# SCH_NFC-Business-card_2025-08-31.net
KiCad netlist of a schematic drawn in EasyEDA
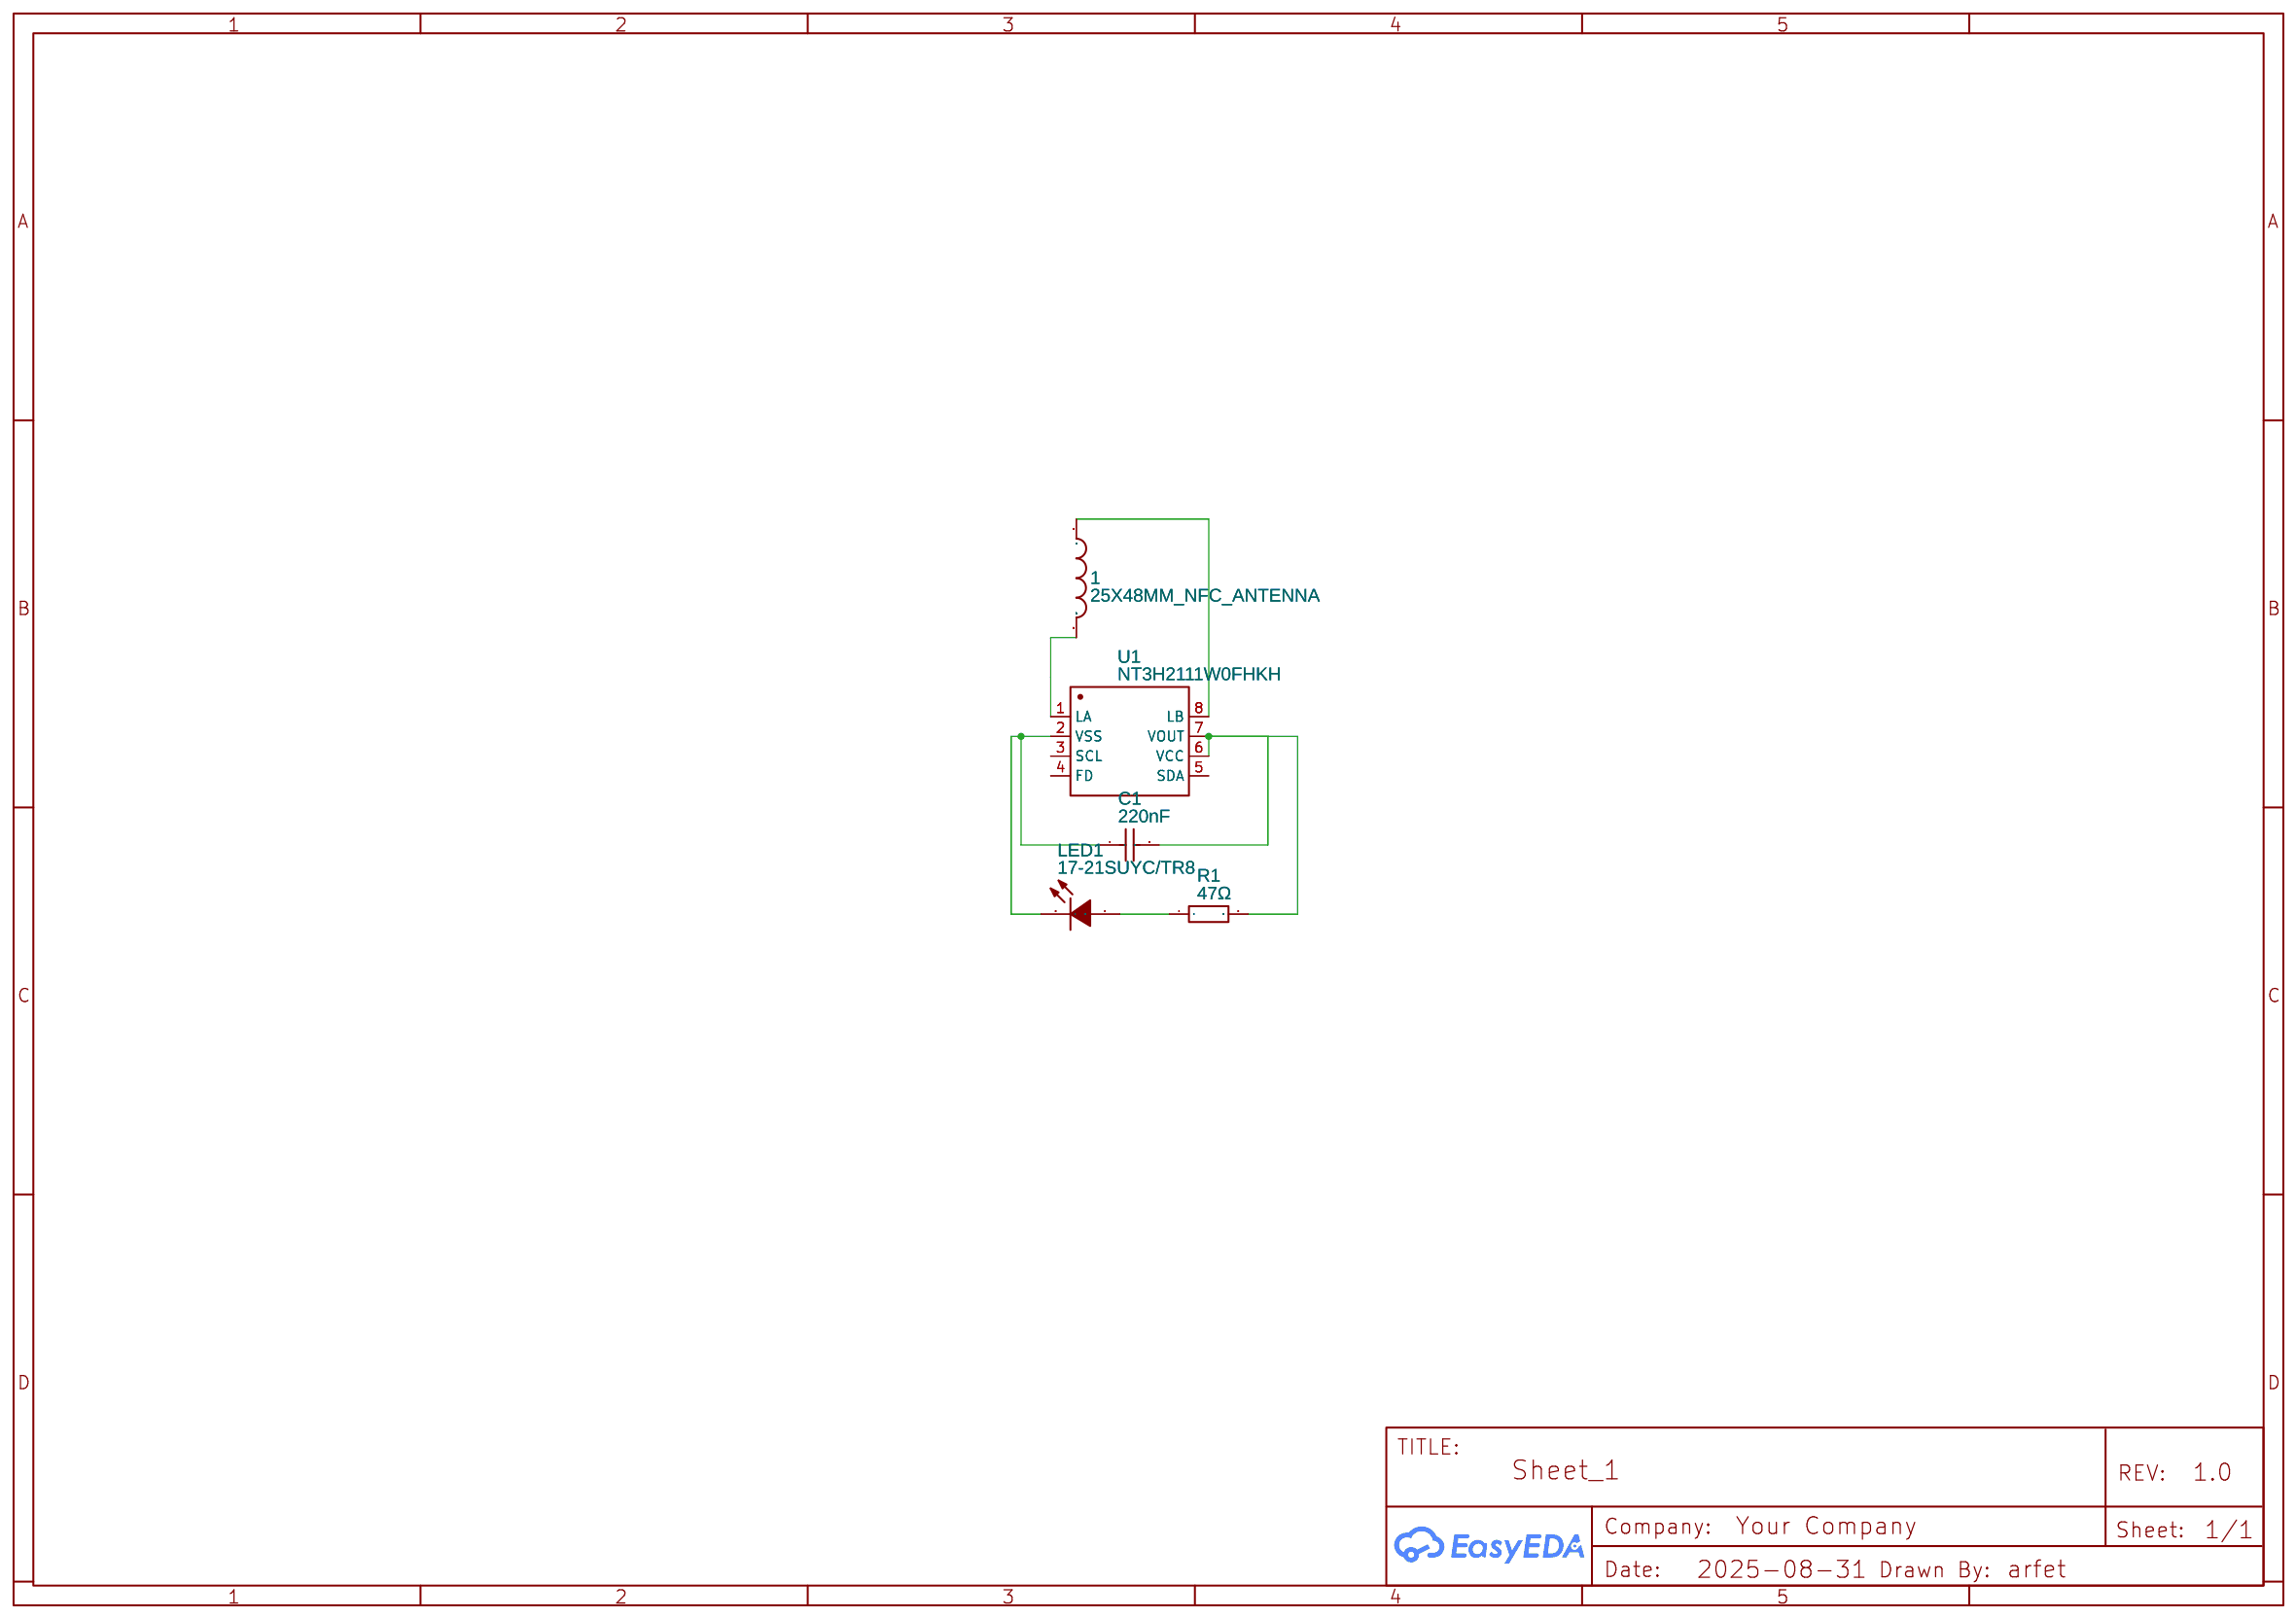
[diagram p0: schematic sheet]

(export (version "E")
  (design (tool "Eeschema 10.0.6"))
  (components
    (comp (ref "1") (value "25X48MM_NFC_ANTENNA") (libsource (lib "") (part "25X48MM_NFC_ANTENNA")))
    (comp (ref "C1")
      (value "220nF")
      (fields
        (field (name "Manufacturer Part") "CL10B224KA8NNNC")
        (field (name "Manufacturer") "SAMSUNG(三星)")
      )
      (libsource (lib "") (part "CL10B224KA8NNNC"))
    )
    (comp (ref "LED1")
      (value "17-21SUYC/TR8")
      (fields (field (name "Manufacturer Part") "KT-0805黄灯") (field (name "Manufacturer") "KENTO"))
      (libsource (lib "") (part "17-21SUYC/TR8"))
    )
    (comp (ref "R1")
      (value "47Ω")
      (fields
        (field (name "Manufacturer Part") "0603WAF470JT5E")
        (field (name "Manufacturer") "UNI-ROYAL(厚声)")
      )
      (libsource (lib "") (part "0603WAF470JT5E"))
    )
    (comp (ref "U1")
      (value "NT3H2111W0FHKH")
      (fields (field (name "Manufacturer") "NXP(恩智浦)"))
      (libsource (lib "") (part "NT3H2111W0FHKH"))
    )
  )
  (nets
    (net (code "1") (name "Net-(LED1-+)") (class "Default")
      (node (ref "LED1") (pin "1") (pinfunction "+_1") (pintype "unspecified"))
      (node (ref "R1") (pin "1") (pinfunction "1_1") (pintype "input"))
    )
    (net (code "2") (name "Net-(LED1--)") (class "Default")
      (node (ref "C1") (pin "1") (pinfunction "1_1") (pintype "input"))
      (node (ref "LED1") (pin "2") (pinfunction "-_2") (pintype "unspecified"))
      (node (ref "U1") (pin "2") (pinfunction "VSS_2") (pintype "unspecified"))
    )
    (net (code "3") (name "Net-(U1-LA)") (class "Default")
      (node (ref "1") (pin "P$2") (pinfunction "P$2_P$2") (pintype "bidirectional"))
      (node (ref "U1") (pin "1") (pinfunction "LA_1") (pintype "unspecified"))
    )
    (net (code "4") (name "Net-(U1-LB)") (class "Default")
      (node (ref "1") (pin "P$1") (pinfunction "P$1_P$1") (pintype "bidirectional"))
      (node (ref "U1") (pin "8") (pinfunction "LB_8") (pintype "unspecified"))
    )
    (net (code "5") (name "Net-(U1-VCC)") (class "Default")
      (node (ref "C1") (pin "2") (pinfunction "2_2") (pintype "input"))
      (node (ref "R1") (pin "2") (pinfunction "2_2") (pintype "input"))
      (node (ref "U1") (pin "6") (pinfunction "VCC_6") (pintype "unspecified"))
      (node (ref "U1") (pin "7") (pinfunction "VOUT_7") (pintype "unspecified"))
    )
    (net (code "6") (name "unconnected-(U1-FD-Pad4)") (class "Default")
      (node (ref "U1") (pin "4") (pinfunction "FD_4") (pintype "unspecified"))
    )
    (net (code "7") (name "unconnected-(U1-SCL-Pad3)") (class "Default")
      (node (ref "U1") (pin "3") (pinfunction "SCL_3") (pintype "unspecified"))
    )
    (net (code "8") (name "unconnected-(U1-SDA-Pad5)") (class "Default")
      (node (ref "U1") (pin "5") (pinfunction "SDA_5") (pintype "unspecified"))
    )
  )
)
